# Proiect_TSC.net
KiCad netlist of a schematic drawn in EAGLE
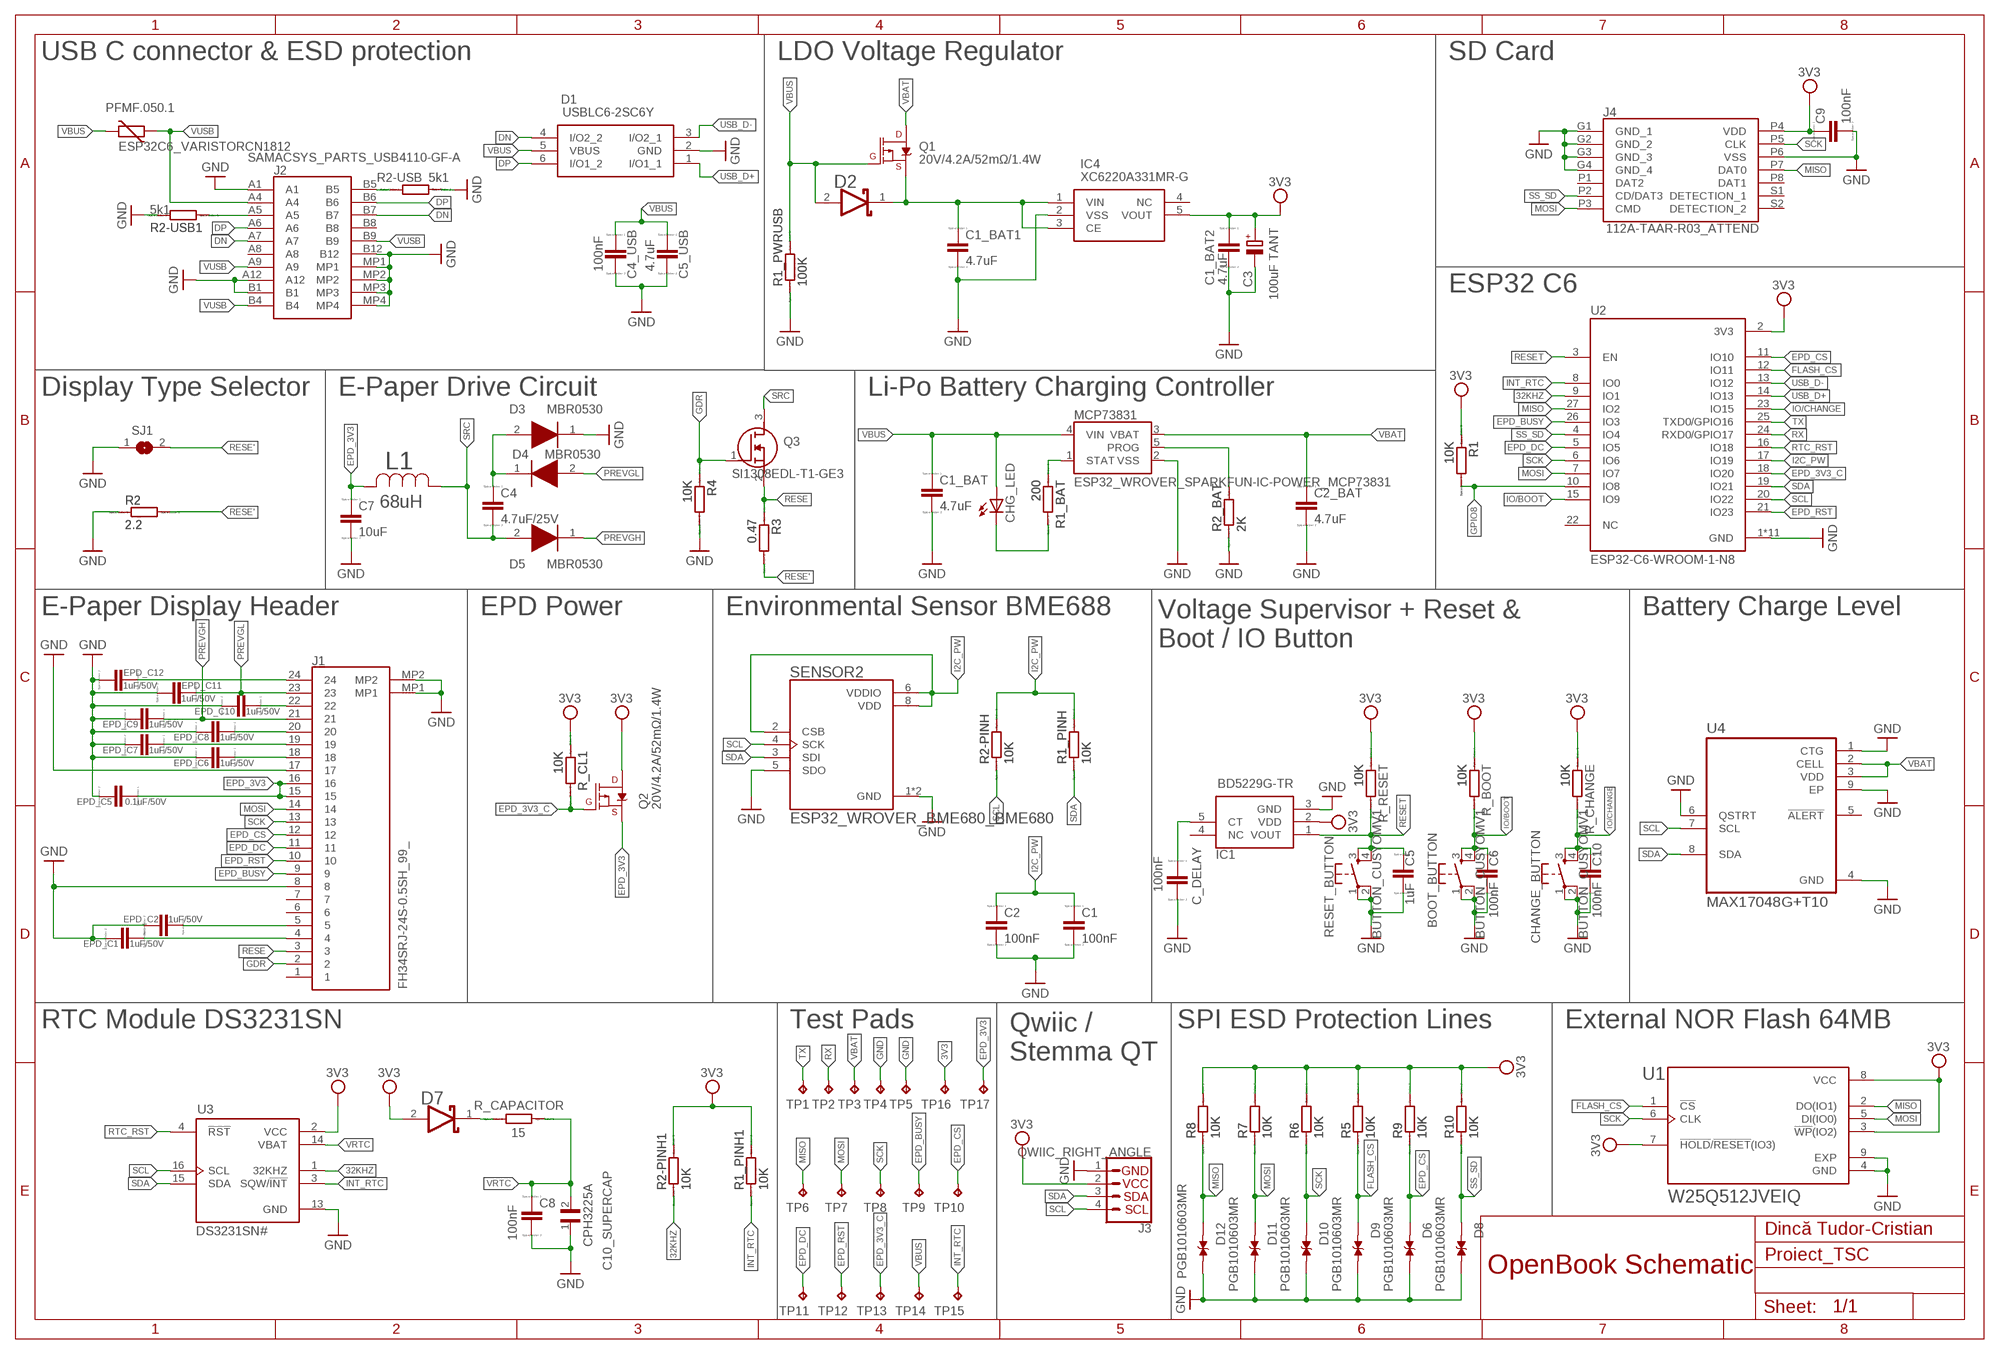
[diagram p0: schematic, sheet 1]

(export (version "E")
  (design (tool "Eeschema 10.0.6"))
  (components
    (comp (ref "BOOT_BUTTON")
      (value "BUTTON_CUSYOMV1")
      (footprint "eagle-import:MYBUTTON")
      (libsource (lib "eagle-import") (part "BUTTON_CUSYOMV1"))
    )
    (comp (ref "C1")
      (value "100nF")
      (footprint "eagle-import:EAGLE-LTSPICE_C0402")
      (libsource (lib "eagle-import") (part "EAGLE-LTSPICE_CC0402"))
    )
    (comp (ref "C1_BAT")
      (value "4.7uF")
      (footprint "eagle-import:EAGLE-LTSPICE_C0402")
      (libsource (lib "eagle-import") (part "EAGLE-LTSPICE_CC0402"))
    )
    (comp (ref "C1_BAT1")
      (value "4.7uF")
      (footprint "eagle-import:EAGLE-LTSPICE_C0402")
      (libsource (lib "eagle-import") (part "ESP32_WROVER_EAGLE-LTSPICE_CC0402"))
    )
    (comp (ref "C1_BAT2")
      (value "4.7uF")
      (footprint "eagle-import:EAGLE-LTSPICE_C0402")
      (libsource (lib "eagle-import") (part "ESP32_WROVER_EAGLE-LTSPICE_CC0402"))
    )
    (comp (ref "C2")
      (value "100nF")
      (footprint "eagle-import:EAGLE-LTSPICE_C0402")
      (libsource (lib "eagle-import") (part "EAGLE-LTSPICE_CC0402"))
    )
    (comp (ref "C2_BAT")
      (value "4.7uF")
      (footprint "eagle-import:EAGLE-LTSPICE_C0402")
      (libsource (lib "eagle-import") (part "EAGLE-LTSPICE_CC0402"))
    )
    (comp (ref "C3")
      (value "100uF TANT")
      (footprint "eagle-import:RCL_CT3528")
      (libsource (lib "eagle-import") (part "RCL_CPOL-EUCT3528"))
    )
    (comp (ref "C4")
      (value "4.7uF/25V")
      (footprint "eagle-import:EAGLE-LTSPICE_C0402")
      (libsource (lib "eagle-import") (part "EAGLE-LTSPICE_CC0402"))
    )
    (comp (ref "C4_USB")
      (value "100nF")
      (footprint "eagle-import:EAGLE-LTSPICE_C0402")
      (libsource (lib "eagle-import") (part "ESP32_WROVER_EAGLE-LTSPICE_CC0402"))
    )
    (comp (ref "C5")
      (value "1uF")
      (footprint "eagle-import:EAGLE-LTSPICE_C0402")
      (libsource (lib "eagle-import") (part "EAGLE-LTSPICE_CC0402"))
    )
    (comp (ref "C5_USB")
      (value "4.7uF")
      (footprint "eagle-import:EAGLE-LTSPICE_C0402")
      (libsource (lib "eagle-import") (part "ESP32_WROVER_EAGLE-LTSPICE_CC0402"))
    )
    (comp (ref "C6")
      (value "100nF")
      (footprint "eagle-import:EAGLE-LTSPICE_C0402")
      (libsource (lib "eagle-import") (part "EAGLE-LTSPICE_CC0402"))
    )
    (comp (ref "C7")
      (value "10uF")
      (footprint "eagle-import:EAGLE-LTSPICE_C0402")
      (libsource (lib "eagle-import") (part "EAGLE-LTSPICE_CC0402"))
    )
    (comp (ref "C8")
      (value "100nF")
      (footprint "eagle-import:EAGLE-LTSPICE_C0402")
      (libsource (lib "eagle-import") (part "EAGLE-LTSPICE_CC0402"))
    )
    (comp (ref "C9")
      (value "100nF")
      (footprint "eagle-import:EAGLE-LTSPICE_C0402")
      (libsource (lib "eagle-import") (part "ESP32_WROVER_EAGLE-LTSPICE_CC0402"))
    )
    (comp (ref "C10")
      (value "100nF")
      (footprint "eagle-import:EAGLE-LTSPICE_C0402")
      (libsource (lib "eagle-import") (part "EAGLE-LTSPICE_CC0402"))
    )
    (comp (ref "C10_SUPERCAP")
      (value "CPH3225A")
      (footprint "eagle-import:CAPCP3225X100N")
      (fields (field (name "MF") "Seiko Instruments"))
      (libsource (lib "eagle-import") (part "CPH3225A"))
    )
    (comp (ref "CHANGE_BUTTON")
      (value "BUTTON_CUSYOMV1")
      (footprint "eagle-import:MYBUTTON")
      (libsource (lib "eagle-import") (part "BUTTON_CUSYOMV1"))
    )
    (comp (ref "CHG_LED")
      (value "ADAFRUIT_LEDCHIP-LED0603")
      (footprint "eagle-import:ADAFRUIT_CHIP-LED0603")
      (libsource (lib "eagle-import") (part "ADAFRUIT_LEDCHIP-LED0603"))
    )
    (comp (ref "C_DELAY")
      (value "100nF")
      (footprint "eagle-import:EAGLE-LTSPICE_C0402")
      (libsource (lib "eagle-import") (part "EAGLE-LTSPICE_CC0402"))
    )
    (comp (ref "D1")
      (value "USBLC6-2SC6Y")
      (footprint "eagle-import:SOT95P280X145-6N")
      (fields (field (name "MF") "STMicroelectronics"))
      (libsource (lib "eagle-import") (part "USBLC6-2SC6Y"))
    )
    (comp (ref "D2")
      (value "ESP32_WROVER_AVX---SD0805S020S1R0_AVX_SD0805S020S1R0_0_0AVX_SD0805S020S1R0_0_0")
      (footprint "eagle-import:ESP32_WROVER_AVX---SD0805S020S1R0_AVX_SD0805S020S1R0_0")
      (fields
        (field (name "DIGIKEY_PART_NUMBER") "478-7800-1-ND")
        (field (name "MF") "AVX")
        (field (name "MOUSER_PART_NUMBER") "581-SD0805S020S1R0")
      )
      (libsource (lib "eagle-import") (part "ESP32_WROVER_AVX---SD0805S020S1R0_AVX_SD0805S020S1R0_0_0AVX_SD0805S020S1R0_0_0"))
    )
    (comp (ref "D3")
      (value "MBR0530")
      (footprint "eagle-import:SOD3716X135N")
      (fields (field (name "MF") "ON Semiconductor"))
      (libsource (lib "eagle-import") (part "MBR0530"))
    )
    (comp (ref "D4")
      (value "MBR0530")
      (footprint "eagle-import:SOD3716X135N")
      (fields (field (name "MF") "ON Semiconductor"))
      (libsource (lib "eagle-import") (part "MBR0530"))
    )
    (comp (ref "D5")
      (value "MBR0530")
      (footprint "eagle-import:SOD3716X135N")
      (fields (field (name "MF") "ON Semiconductor"))
      (libsource (lib "eagle-import") (part "MBR0530"))
    )
    (comp (ref "D6")
      (value "PGB1010603MR")
      (footprint "eagle-import:DIOC1608X36N")
      (fields (field (name "MF") "Littelfuse Inc."))
      (libsource (lib "eagle-import") (part "PGB1010603MR"))
    )
    (comp (ref "D7")
      (value "ESP32_WROVER_AVX---SD0805S020S1R0_AVX_SD0805S020S1R0_0_0AVX_SD0805S020S1R0_0_0")
      (footprint "eagle-import:ESP32_WROVER_AVX---SD0805S020S1R0_AVX_SD0805S020S1R0_0")
      (fields
        (field (name "DIGIKEY_PART_NUMBER") "478-7800-1-ND")
        (field (name "MF") "AVX")
        (field (name "MOUSER_PART_NUMBER") "581-SD0805S020S1R0")
      )
      (libsource (lib "eagle-import") (part "ESP32_WROVER_AVX---SD0805S020S1R0_AVX_SD0805S020S1R0_0_0AVX_SD0805S020S1R0_0_0"))
    )
    (comp (ref "D8")
      (value "PGB1010603MR")
      (footprint "eagle-import:DIOC1608X36N")
      (fields (field (name "MF") "Littelfuse Inc."))
      (libsource (lib "eagle-import") (part "PGB1010603MR"))
    )
    (comp (ref "D9")
      (value "PGB1010603MR")
      (footprint "eagle-import:DIOC1608X36N")
      (fields (field (name "MF") "Littelfuse Inc."))
      (libsource (lib "eagle-import") (part "PGB1010603MR"))
    )
    (comp (ref "D10")
      (value "PGB1010603MR")
      (footprint "eagle-import:DIOC1608X36N")
      (fields (field (name "MF") "Littelfuse Inc."))
      (libsource (lib "eagle-import") (part "PGB1010603MR"))
    )
    (comp (ref "D11")
      (value "PGB1010603MR")
      (footprint "eagle-import:DIOC1608X36N")
      (fields (field (name "MF") "Littelfuse Inc."))
      (libsource (lib "eagle-import") (part "PGB1010603MR"))
    )
    (comp (ref "D12")
      (value "PGB1010603MR")
      (footprint "eagle-import:DIOC1608X36N")
      (fields (field (name "MF") "Littelfuse Inc."))
      (libsource (lib "eagle-import") (part "PGB1010603MR"))
    )
    (comp (ref "EPD_C1")
      (value "1uF/50V")
      (footprint "eagle-import:EAGLE-LTSPICE_C0402")
      (libsource (lib "eagle-import") (part "EAGLE-LTSPICE_CC0402"))
    )
    (comp (ref "EPD_C2")
      (value "1uF/50V")
      (footprint "eagle-import:EAGLE-LTSPICE_C0402")
      (libsource (lib "eagle-import") (part "EAGLE-LTSPICE_CC0402"))
    )
    (comp (ref "EPD_C5")
      (value "0.1uF/50V")
      (footprint "eagle-import:EAGLE-LTSPICE_C0402")
      (libsource (lib "eagle-import") (part "EAGLE-LTSPICE_CC0402"))
    )
    (comp (ref "EPD_C6")
      (value "1uF/50V")
      (footprint "eagle-import:EAGLE-LTSPICE_C0402")
      (libsource (lib "eagle-import") (part "EAGLE-LTSPICE_CC0402"))
    )
    (comp (ref "EPD_C7")
      (value "1uF/50V")
      (footprint "eagle-import:EAGLE-LTSPICE_C0402")
      (libsource (lib "eagle-import") (part "EAGLE-LTSPICE_CC0402"))
    )
    (comp (ref "EPD_C8")
      (value "1uF/50V")
      (footprint "eagle-import:EAGLE-LTSPICE_C0402")
      (libsource (lib "eagle-import") (part "EAGLE-LTSPICE_CC0402"))
    )
    (comp (ref "EPD_C9")
      (value "1uF/50V")
      (footprint "eagle-import:EAGLE-LTSPICE_C0402")
      (libsource (lib "eagle-import") (part "EAGLE-LTSPICE_CC0402"))
    )
    (comp (ref "EPD_C10")
      (value "1uF/50V")
      (footprint "eagle-import:EAGLE-LTSPICE_C0402")
      (libsource (lib "eagle-import") (part "EAGLE-LTSPICE_CC0402"))
    )
    (comp (ref "EPD_C11")
      (value "1uF/50V")
      (footprint "eagle-import:EAGLE-LTSPICE_C0402")
      (libsource (lib "eagle-import") (part "EAGLE-LTSPICE_CC0402"))
    )
    (comp (ref "EPD_C12")
      (value "1uF/50V")
      (footprint "eagle-import:EAGLE-LTSPICE_C0402")
      (libsource (lib "eagle-import") (part "EAGLE-LTSPICE_CC0402"))
    )
    (comp (ref "IC1")
      (value "BD5229G-TR")
      (footprint "eagle-import:SOT95P280X125-5N")
      (fields (field (name "MOUSER_PART_NUMBER") "755-BD5229G-TR"))
      (libsource (lib "eagle-import") (part "BD5229G-TR"))
    )
    (comp (ref "IC4")
      (value "XC6220A331MR-G")
      (footprint "eagle-import:SOT95P280X120-5N")
      (fields (field (name "MOUSER_PART_NUMBER") "865-XC6220A331MR-G"))
      (libsource (lib "eagle-import") (part "XC6220A331MR-G"))
    )
    (comp (ref "J1")
      (value "FH34SRJ-24S-0.5SH_99_")
      (footprint "eagle-import:FH34SRJ24S05SH99")
      (fields
        (field (name "MANUFACTURER_PART_NUMBER") "FH34SRJ-24S-0.5SH(99)")
        (field (name "MOUSER_PART_NUMBER") "798-FH34SRJ24S05SH99")
      )
      (libsource (lib "eagle-import") (part "FH34SRJ-24S-0.5SH_99_"))
    )
    (comp (ref "J2")
      (value "SAMACSYS_PARTS_USB4110-GF-A")
      (footprint "eagle-import:SAMACSYS_PARTS_USB4110GFA")
      (fields
        (field (name "MANUFACTURER_PART_NUMBER") "USB4110-GF-A")
        (field (name "MOUSER_PART_NUMBER") "640-USB4110-GF-A")
      )
      (libsource (lib "eagle-import") (part "SAMACSYS_PARTS_USB4110-GF-A"))
    )
    (comp (ref "J3")
      (value "QWIIC_RIGHT_ANGLE")
      (footprint "eagle-import:JST04_1MM_RA")
      (libsource (lib "eagle-import") (part "QWIIC_CONNECTORJS-1MM"))
    )
    (comp (ref "J4")
      (value "112A-TAAR-R03_ATTEND")
      (footprint "eagle-import:112ATAARR03ATTEND")
      (fields (field (name "MANUFACTURER_PART_NUMBER") "112A-TAAR-R03 ATTEND"))
      (libsource (lib "eagle-import") (part "112A-TAAR-R03_ATTEND"))
    )
    (comp (ref "L1")
      (value "68uH")
      (footprint "eagle-import:IND_4828-WE-TPC_WRE")
      (fields
        (field (name "MANUFACTURER_PART_NUMBER") "744043680")
        (field (name "COPYRIGHT") "Copyright (C) 2024 Ultra Librarian. All rights reserved.")
      )
      (libsource (lib "eagle-import") (part "744043680IND_4828-WE-TPC_WRE"))
    )
    (comp (ref "MCP73831")
      (value "ESP32_WROVER_SPARKFUN-IC-POWER_MCP73831")
      (footprint "eagle-import:ESP32_WROVER_SPARKFUN-IC-POWER_SOT23-5")
      (libsource (lib "eagle-import") (part "ESP32_WROVER_SPARKFUN-IC-POWER_MCP73831"))
    )
    (comp (ref "PFMF.050.1")
      (value "ESP32C6_VARISTORCN1812")
      (footprint "eagle-import:ESP32C6_VARISTOR_CT_CN1812")
      (libsource (lib "eagle-import") (part "ESP32C6_VARISTORCN1812"))
    )
    (comp (ref "Q1")
      (value "20V/4.2A/52mΩ/1.4W")
      (footprint "eagle-import:ESP32_WROVER_SPARKFUN-DISCRETESEMI_SOT23-3")
      (libsource (lib "eagle-import") (part "ESP32_WROVER_SPARKFUN-DISCRETESEMI_MOSFET_PCH-DMG2305UX-7"))
    )
    (comp (ref "Q2")
      (value "20V/4.2A/52mΩ/1.4W")
      (footprint "eagle-import:ESP32_WROVER_SPARKFUN-DISCRETESEMI_SOT23-3")
      (libsource (lib "eagle-import") (part "ESP32_WROVER_SPARKFUN-DISCRETESEMI_MOSFET_PCH-DMG2305UX-7"))
    )
    (comp (ref "Q3")
      (value "SI1308EDL-T1-GE3")
      (footprint "eagle-import:SOT65P210X110-3N")
      (fields (field (name "MF") "Vishay Siliconix"))
      (libsource (lib "eagle-import") (part "SI1308EDL-T1-GE3"))
    )
    (comp (ref "R1")
      (value "10K")
      (footprint "eagle-import:ESP32_WROVER_EAGLE-LTSPICE_R0402")
      (libsource (lib "eagle-import") (part "ESP32_WROVER_EAGLE-LTSPICE_RR0402"))
    )
    (comp (ref "R1_BAT")
      (value "200")
      (footprint "eagle-import:ESP32_WROVER_EAGLE-LTSPICE_R0402")
      (libsource (lib "eagle-import") (part "ESP32_WROVER_EAGLE-LTSPICE_RR0402"))
    )
    (comp (ref "R1_PINH")
      (value "10K")
      (footprint "eagle-import:ESP32_WROVER_EAGLE-LTSPICE_R0402")
      (libsource (lib "eagle-import") (part "ESP32_WROVER_EAGLE-LTSPICE_RR0402"))
    )
    (comp (ref "R1_PINH1")
      (value "10K")
      (footprint "eagle-import:ESP32_WROVER_EAGLE-LTSPICE_R0402")
      (libsource (lib "eagle-import") (part "ESP32_WROVER_EAGLE-LTSPICE_RR0402"))
    )
    (comp (ref "R1_PWRUSB")
      (value "100K")
      (footprint "eagle-import:ESP32_WROVER_EAGLE-LTSPICE_R0402")
      (libsource (lib "eagle-import") (part "ESP32_WROVER_EAGLE-LTSPICE_RR0402"))
    )
    (comp (ref "R2")
      (value "2.2")
      (footprint "eagle-import:ESP32_WROVER_EAGLE-LTSPICE_R0402")
      (libsource (lib "eagle-import") (part "ESP32_WROVER_EAGLE-LTSPICE_RR0402"))
    )
    (comp (ref "R2-PINH")
      (value "10K")
      (footprint "eagle-import:ESP32_WROVER_EAGLE-LTSPICE_R0402")
      (libsource (lib "eagle-import") (part "ESP32_WROVER_EAGLE-LTSPICE_RR0402"))
    )
    (comp (ref "R2-PINH1")
      (value "10K")
      (footprint "eagle-import:ESP32_WROVER_EAGLE-LTSPICE_R0402")
      (libsource (lib "eagle-import") (part "ESP32_WROVER_EAGLE-LTSPICE_RR0402"))
    )
    (comp (ref "R2-USB")
      (value "5k1")
      (footprint "eagle-import:ESP32_WROVER_EAGLE-LTSPICE_R0402")
      (libsource (lib "eagle-import") (part "ESP32_WROVER_EAGLE-LTSPICE_RR0402"))
    )
    (comp (ref "R2-USB1")
      (value "5k1")
      (footprint "eagle-import:ESP32_WROVER_EAGLE-LTSPICE_R0402")
      (libsource (lib "eagle-import") (part "ESP32_WROVER_EAGLE-LTSPICE_RR0402"))
    )
    (comp (ref "R2_BAT")
      (value "2K")
      (footprint "eagle-import:ESP32_WROVER_EAGLE-LTSPICE_R0402")
      (libsource (lib "eagle-import") (part "ESP32_WROVER_EAGLE-LTSPICE_RR0402"))
    )
    (comp (ref "R3")
      (value "0.47")
      (footprint "eagle-import:ESP32_WROVER_EAGLE-LTSPICE_R0402")
      (libsource (lib "eagle-import") (part "ESP32_WROVER_EAGLE-LTSPICE_RR0402"))
    )
    (comp (ref "R4")
      (value "10K")
      (footprint "eagle-import:ESP32_WROVER_EAGLE-LTSPICE_R0402")
      (libsource (lib "eagle-import") (part "ESP32_WROVER_EAGLE-LTSPICE_RR0402"))
    )
    (comp (ref "R5")
      (value "10K")
      (footprint "eagle-import:ESP32_WROVER_EAGLE-LTSPICE_R0402")
      (libsource (lib "eagle-import") (part "ESP32_WROVER_EAGLE-LTSPICE_RR0402"))
    )
    (comp (ref "R6")
      (value "10K")
      (footprint "eagle-import:ESP32_WROVER_EAGLE-LTSPICE_R0402")
      (libsource (lib "eagle-import") (part "ESP32_WROVER_EAGLE-LTSPICE_RR0402"))
    )
    (comp (ref "R7")
      (value "10K")
      (footprint "eagle-import:ESP32_WROVER_EAGLE-LTSPICE_R0402")
      (libsource (lib "eagle-import") (part "ESP32_WROVER_EAGLE-LTSPICE_RR0402"))
    )
    (comp (ref "R8")
      (value "10K")
      (footprint "eagle-import:ESP32_WROVER_EAGLE-LTSPICE_R0402")
      (libsource (lib "eagle-import") (part "ESP32_WROVER_EAGLE-LTSPICE_RR0402"))
    )
    (comp (ref "R9")
      (value "10K")
      (footprint "eagle-import:ESP32_WROVER_EAGLE-LTSPICE_R0402")
      (libsource (lib "eagle-import") (part "ESP32_WROVER_EAGLE-LTSPICE_RR0402"))
    )
    (comp (ref "R10")
      (value "10K")
      (footprint "eagle-import:ESP32_WROVER_EAGLE-LTSPICE_R0402")
      (libsource (lib "eagle-import") (part "ESP32_WROVER_EAGLE-LTSPICE_RR0402"))
    )
    (comp (ref "RESET_BUTTON")
      (value "BUTTON_CUSYOMV1")
      (footprint "eagle-import:MYBUTTON")
      (libsource (lib "eagle-import") (part "BUTTON_CUSYOMV1"))
    )
    (comp (ref "R_BOOT")
      (value "10K")
      (footprint "eagle-import:ESP32_WROVER_EAGLE-LTSPICE_R0402")
      (libsource (lib "eagle-import") (part "ESP32_WROVER_EAGLE-LTSPICE_RR0402"))
    )
    (comp (ref "R_CAPACITOR")
      (value "15")
      (footprint "eagle-import:ESP32_WROVER_EAGLE-LTSPICE_R0402")
      (libsource (lib "eagle-import") (part "ESP32_WROVER_EAGLE-LTSPICE_RR0402"))
    )
    (comp (ref "R_CHANGE")
      (value "10K")
      (footprint "eagle-import:ESP32_WROVER_EAGLE-LTSPICE_R0402")
      (libsource (lib "eagle-import") (part "ESP32_WROVER_EAGLE-LTSPICE_RR0402"))
    )
    (comp (ref "R_CL1")
      (value "10K")
      (footprint "eagle-import:ESP32_WROVER_EAGLE-LTSPICE_R0402")
      (libsource (lib "eagle-import") (part "ESP32_WROVER_EAGLE-LTSPICE_RR0402"))
    )
    (comp (ref "R_RESET")
      (value "10K")
      (footprint "eagle-import:ESP32_WROVER_EAGLE-LTSPICE_R0402")
      (libsource (lib "eagle-import") (part "ESP32_WROVER_EAGLE-LTSPICE_RR0402"))
    )
    (comp (ref "SENSOR2")
      (value "ESP32_WROVER_BME680_BME680")
      (footprint "eagle-import:ESP32_WROVER_BME680_PSON80P300X300X100-8N")
      (fields (field (name "MF") "Bosch Sensortec") (field (name "MP") "BME680"))
      (libsource (lib "eagle-import") (part "ESP32_WROVER_BME680_BME680"))
    )
    (comp (ref "SJ1") (value "SJ") (footprint "eagle-import:SJ") (libsource (lib "eagle-import") (part "SJ")))
    (comp (ref "TP1")
      (value "TPTP20R")
      (footprint "eagle-import:TP20R")
      (libsource (lib "eagle-import") (part "TPTP20R"))
    )
    (comp (ref "TP2")
      (value "TPTP20R")
      (footprint "eagle-import:TP20R")
      (libsource (lib "eagle-import") (part "TPTP20R"))
    )
    (comp (ref "TP3")
      (value "TPTP20R")
      (footprint "eagle-import:TP20R")
      (libsource (lib "eagle-import") (part "TPTP20R"))
    )
    (comp (ref "TP4")
      (value "TPTP20R")
      (footprint "eagle-import:TP20R")
      (libsource (lib "eagle-import") (part "TPTP20R"))
    )
    (comp (ref "TP5")
      (value "TPTP20R")
      (footprint "eagle-import:TP20R")
      (libsource (lib "eagle-import") (part "TPTP20R"))
    )
    (comp (ref "TP6")
      (value "TPTP20R")
      (footprint "eagle-import:TP20R")
      (libsource (lib "eagle-import") (part "TPTP20R"))
    )
    (comp (ref "TP7")
      (value "TPTP20R")
      (footprint "eagle-import:TP20R")
      (libsource (lib "eagle-import") (part "TPTP20R"))
    )
    (comp (ref "TP8")
      (value "TPTP20R")
      (footprint "eagle-import:TP20R")
      (libsource (lib "eagle-import") (part "TPTP20R"))
    )
    (comp (ref "TP9")
      (value "TPTP20R")
      (footprint "eagle-import:TP20R")
      (libsource (lib "eagle-import") (part "TPTP20R"))
    )
    (comp (ref "TP10")
      (value "TPTP20R")
      (footprint "eagle-import:TP20R")
      (libsource (lib "eagle-import") (part "TPTP20R"))
    )
    (comp (ref "TP11")
      (value "TPTP20R")
      (footprint "eagle-import:TP20R")
      (libsource (lib "eagle-import") (part "TPTP20R"))
    )
    (comp (ref "TP12")
      (value "TPTP20R")
      (footprint "eagle-import:TP20R")
      (libsource (lib "eagle-import") (part "TPTP20R"))
    )
    (comp (ref "TP13")
      (value "TPTP20R")
      (footprint "eagle-import:TP20R")
      (libsource (lib "eagle-import") (part "TPTP20R"))
    )
    (comp (ref "TP14")
      (value "TPTP20R")
      (footprint "eagle-import:TP20R")
      (libsource (lib "eagle-import") (part "TPTP20R"))
    )
    (comp (ref "TP15")
      (value "TPTP20R")
      (footprint "eagle-import:TP20R")
      (libsource (lib "eagle-import") (part "TPTP20R"))
    )
    (comp (ref "TP16")
      (value "TPTP20R")
      (footprint "eagle-import:TP20R")
      (libsource (lib "eagle-import") (part "TPTP20R"))
    )
    (comp (ref "TP17")
      (value "TPTP20R")
      (footprint "eagle-import:TP20R")
      (libsource (lib "eagle-import") (part "TPTP20R"))
    )
    (comp (ref "U1")
      (value "W25Q512JVEIQ")
      (footprint "eagle-import:SON127P600X800X80-9N")
      (fields (field (name "MF") "Winbond Electronics"))
      (libsource (lib "eagle-import") (part "W25Q512JVEIQ"))
    )
    (comp (ref "U2")
      (value "ESP32-C6-WROOM-1-N8")
      (footprint "eagle-import:XCVR_ESP32-C6-WROOM-1-N8")
      (fields (field (name "MF") "Espressif Systems"))
      (libsource (lib "eagle-import") (part "ESP32-C6-WROOM-1-N8"))
    )
    (comp (ref "U3")
      (value "DS3231SN#")
      (footprint "eagle-import:SOIC127P1032X265-16N")
      (fields (field (name "MF") "Analog Devices"))
      (libsource (lib "eagle-import") (part "DS3231SN#"))
    )
    (comp (ref "U4")
      (value "MAX17048G+T10")
      (footprint "eagle-import:SON50P200X200X80-9N")
      (fields (field (name "MF") "Analog Devices"))
      (libsource (lib "eagle-import") (part "MAX17048G+T10"))
    )
  )
  (nets
    (net (code "1") (name "3V3") (class "Default")
      (node (ref "C1_BAT2") (pin "1") (pinfunction "1_1") (pintype "passive"))
      (node (ref "C3") (pin "+") (pinfunction "+_+") (pintype "passive"))
      (node (ref "C9") (pin "1") (pinfunction "1_1") (pintype "passive"))
      (node (ref "D7") (pin "2") (pinfunction "ANODE_2") (pintype "bidirectional"))
      (node (ref "IC1") (pin "2") (pinfunction "VDD_2") (pintype "bidirectional"))
      (node (ref "IC4") (pin "5") (pinfunction "VOUT_5") (pintype "bidirectional"))
      (node (ref "J3") (pin "2") (pinfunction "2_2") (pintype "power_in"))
      (node (ref "J4") (pin "P4") (pinfunction "VDD_P4") (pintype "bidirectional"))
      (node (ref "Q2") (pin "3") (pinfunction "D_3") (pintype "bidirectional"))
      (node (ref "R1") (pin "1") (pinfunction "1_1") (pintype "passive"))
      (node (ref "R10") (pin "2") (pinfunction "2_2") (pintype "passive"))
      (node (ref "R1_PINH1") (pin "2") (pinfunction "2_2") (pintype "passive"))
      (node (ref "R2-PINH1") (pin "2") (pinfunction "2_2") (pintype "passive"))
      (node (ref "R5") (pin "2") (pinfunction "2_2") (pintype "passive"))
      (node (ref "R6") (pin "2") (pinfunction "2_2") (pintype "passive"))
      (node (ref "R7") (pin "2") (pinfunction "2_2") (pintype "passive"))
      (node (ref "R8") (pin "2") (pinfunction "2_2") (pintype "passive"))
      (node (ref "R9") (pin "2") (pinfunction "2_2") (pintype "passive"))
      (node (ref "R_BOOT") (pin "1") (pinfunction "1_1") (pintype "passive"))
      (node (ref "R_CHANGE") (pin "1") (pinfunction "1_1") (pintype "passive"))
      (node (ref "R_CL1") (pin "1") (pinfunction "1_1") (pintype "passive"))
      (node (ref "R_RESET") (pin "1") (pinfunction "1_1") (pintype "passive"))
      (node (ref "TP16") (pin "TP") (pinfunction "TP_TP") (pintype "input"))
      (node (ref "U1") (pin "3") (pinfunction "~{WP}(IO2)_3") (pintype "bidirectional"))
      (node (ref "U1") (pin "7") (pinfunction "~{HOLD}/~{RESET}(IO3)_7") (pintype "bidirectional"))
      (node (ref "U1") (pin "8") (pinfunction "VCC_8") (pintype "power_in"))
      (node (ref "U2") (pin "2") (pinfunction "3V3_2") (pintype "power_in"))
      (node (ref "U3") (pin "2") (pinfunction "VCC_2") (pintype "power_in"))
    )
    (net (code "2") (name "32KHZ") (class "Default")
      (node (ref "R2-PINH1") (pin "1") (pinfunction "1_1") (pintype "passive"))
      (node (ref "U2") (pin "9") (pinfunction "IO1_9") (pintype "bidirectional"))
      (node (ref "U3") (pin "1") (pinfunction "32KHZ_1") (pintype "output"))
    )
    (net (code "3") (name "DN") (class "Default")
      (node (ref "D1") (pin "4") (pinfunction "I/O2_2_4") (pintype "bidirectional"))
      (node (ref "J2") (pin "A7") (pinfunction "A7_A7") (pintype "bidirectional"))
      (node (ref "J2") (pin "B7") (pinfunction "B7_B7") (pintype "bidirectional"))
    )
    (net (code "4") (name "DP") (class "Default")
      (node (ref "D1") (pin "6") (pinfunction "I/O1_2_6") (pintype "bidirectional"))
      (node (ref "J2") (pin "A6") (pinfunction "A6_A6") (pintype "bidirectional"))
      (node (ref "J2") (pin "B6") (pinfunction "B6_B6") (pintype "bidirectional"))
    )
    (net (code "5") (name "EPD_3V3") (class "Default")
      (node (ref "C7") (pin "1") (pinfunction "1_1") (pintype "passive"))
      (node (ref "EPD_C5") (pin "1") (pinfunction "1_1") (pintype "passive"))
      (node (ref "J1") (pin "15") (pinfunction "15_15") (pintype "bidirectional"))
      (node (ref "J1") (pin "16") (pinfunction "16_16") (pintype "bidirectional"))
      (node (ref "L1") (pin "2") (pinfunction "2_2") (pintype "passive"))
      (node (ref "Q2") (pin "2") (pinfunction "S_2") (pintype "bidirectional"))
      (node (ref "TP17") (pin "TP") (pinfunction "TP_TP") (pintype "input"))
    )
    (net (code "6") (name "EPD_3V3_C") (class "Default")
      (node (ref "Q2") (pin "1") (pinfunction "G_1") (pintype "bidirectional"))
      (node (ref "R_CL1") (pin "2") (pinfunction "2_2") (pintype "passive"))
      (node (ref "TP13") (pin "TP") (pinfunction "TP_TP") (pintype "input"))
      (node (ref "U2") (pin "18") (pinfunction "IO20_18") (pintype "bidirectional"))
    )
    (net (code "7") (name "EPD_BUSY") (class "Default")
      (node (ref "J1") (pin "9") (pinfunction "9_9") (pintype "bidirectional"))
      (node (ref "TP9") (pin "TP") (pinfunction "TP_TP") (pintype "input"))
      (node (ref "U2") (pin "26") (pinfunction "IO3_26") (pintype "bidirectional"))
    )
    (net (code "8") (name "EPD_CS") (class "Default")
      (node (ref "D6") (pin "1") (pinfunction "1_1") (pintype "passive"))
      (node (ref "J1") (pin "12") (pinfunction "12_12") (pintype "bidirectional"))
      (node (ref "R9") (pin "1") (pinfunction "1_1") (pintype "passive"))
      (node (ref "TP10") (pin "TP") (pinfunction "TP_TP") (pintype "input"))
      (node (ref "U2") (pin "11") (pinfunction "IO10_11") (pintype "bidirectional"))
    )
    (net (code "9") (name "EPD_DC") (class "Default")
      (node (ref "J1") (pin "11") (pinfunction "11_11") (pintype "bidirectional"))
      (node (ref "TP11") (pin "TP") (pinfunction "TP_TP") (pintype "input"))
      (node (ref "U2") (pin "5") (pinfunction "IO5_5") (pintype "bidirectional"))
    )
    (net (code "10") (name "EPD_RST") (class "Default")
      (node (ref "J1") (pin "10") (pinfunction "10_10") (pintype "bidirectional"))
      (node (ref "TP12") (pin "TP") (pinfunction "TP_TP") (pintype "input"))
      (node (ref "U2") (pin "21") (pinfunction "IO23_21") (pintype "bidirectional"))
    )
    (net (code "11") (name "FLASH_CS") (class "Default")
      (node (ref "D9") (pin "1") (pinfunction "1_1") (pintype "passive"))
      (node (ref "R5") (pin "1") (pinfunction "1_1") (pintype "passive"))
      (node (ref "U1") (pin "1") (pinfunction "~{CS}_1") (pintype "input"))
      (node (ref "U2") (pin "12") (pinfunction "IO11_12") (pintype "bidirectional"))
    )
    (net (code "12") (name "GDR") (class "Default")
      (node (ref "J1") (pin "2") (pinfunction "2_2") (pintype "bidirectional"))
      (node (ref "Q3") (pin "1") (pinfunction "G_1") (pintype "bidirectional"))
      (node (ref "R4") (pin "1") (pinfunction "1_1") (pintype "passive"))
    )
    (net (code "13") (name "GND") (class "Default")
      (node (ref "BOOT_BUTTON") (pin "1") (pinfunction "1_1") (pintype "passive"))
      (node (ref "BOOT_BUTTON") (pin "2") (pinfunction "2_2") (pintype "passive"))
      (node (ref "C1") (pin "2") (pinfunction "2_2") (pintype "passive"))
      (node (ref "C10") (pin "2") (pinfunction "2_2") (pintype "passive"))
      (node (ref "C10_SUPERCAP") (pin "1") (pinfunction "1_1") (pintype "passive"))
      (node (ref "C1_BAT") (pin "2") (pinfunction "2_2") (pintype "passive"))
      (node (ref "C1_BAT1") (pin "2") (pinfunction "2_2") (pintype "passive"))
      (node (ref "C1_BAT2") (pin "2") (pinfunction "2_2") (pintype "passive"))
      (node (ref "C2") (pin "2") (pinfunction "2_2") (pintype "passive"))
      (node (ref "C2_BAT") (pin "2") (pinfunction "2_2") (pintype "passive"))
      (node (ref "C3") (pin "-") (pinfunction "-_-") (pintype "passive"))
      (node (ref "C4_USB") (pin "2") (pinfunction "2_2") (pintype "passive"))
      (node (ref "C5") (pin "2") (pinfunction "2_2") (pintype "passive"))
      (node (ref "C5_USB") (pin "2") (pinfunction "2_2") (pintype "passive"))
      (node (ref "C6") (pin "2") (pinfunction "2_2") (pintype "passive"))
      (node (ref "C7") (pin "2") (pinfunction "2_2") (pintype "passive"))
      (node (ref "C8") (pin "2") (pinfunction "2_2") (pintype "passive"))
      (node (ref "C9") (pin "2") (pinfunction "2_2") (pintype "passive"))
      (node (ref "CHANGE_BUTTON") (pin "1") (pinfunction "1_1") (pintype "passive"))
      (node (ref "CHANGE_BUTTON") (pin "2") (pinfunction "2_2") (pintype "passive"))
      (node (ref "C_DELAY") (pin "2") (pinfunction "2_2") (pintype "passive"))
      (node (ref "D1") (pin "2") (pinfunction "GND_2") (pintype "bidirectional"))
      (node (ref "D10") (pin "2") (pinfunction "2_2") (pintype "passive"))
      (node (ref "D11") (pin "2") (pinfunction "2_2") (pintype "passive"))
      (node (ref "D12") (pin "2") (pinfunction "2_2") (pintype "passive"))
      (node (ref "D3") (pin "1") (pinfunction "K_1") (pintype "bidirectional"))
      (node (ref "D6") (pin "2") (pinfunction "2_2") (pintype "passive"))
      (node (ref "D8") (pin "2") (pinfunction "2_2") (pintype "passive"))
      (node (ref "D9") (pin "2") (pinfunction "2_2") (pintype "passive"))
      (node (ref "EPD_C1") (pin "2") (pinfunction "2_2") (pintype "passive"))
      (node (ref "EPD_C10") (pin "2") (pinfunction "2_2") (pintype "passive"))
      (node (ref "EPD_C11") (pin "2") (pinfunction "2_2") (pintype "passive"))
      (node (ref "EPD_C12") (pin "2") (pinfunction "2_2") (pintype "passive"))
      (node (ref "EPD_C2") (pin "2") (pinfunction "2_2") (pintype "passive"))
      (node (ref "EPD_C5") (pin "2") (pinfunction "2_2") (pintype "passive"))
      (node (ref "EPD_C6") (pin "2") (pinfunction "2_2") (pintype "passive"))
      (node (ref "EPD_C7") (pin "2") (pinfunction "2_2") (pintype "passive"))
      (node (ref "EPD_C8") (pin "2") (pinfunction "2_2") (pintype "passive"))
      (node (ref "EPD_C9") (pin "2") (pinfunction "2_2") (pintype "passive"))
      (node (ref "IC1") (pin "3") (pinfunction "GND_3") (pintype "bidirectional"))
      (node (ref "IC4") (pin "2") (pinfunction "VSS_2") (pintype "bidirectional"))
      (node (ref "J1") (pin "17") (pinfunction "17_17") (pintype "bidirectional"))
      (node (ref "J1") (pin "8") (pinfunction "8_8") (pintype "bidirectional"))
      (node (ref "J1") (pin "MP1") (pinfunction "MP1_MP1") (pintype "bidirectional"))
      (node (ref "J1") (pin "MP2") (pinfunction "MP2_MP2") (pintype "bidirectional"))
      (node (ref "J2") (pin "A1") (pinfunction "A1_A1") (pintype "bidirectional"))
      (node (ref "J2") (pin "A12") (pinfunction "A12_A12") (pintype "bidirectional"))
      (node (ref "J2") (pin "B1") (pinfunction "B1_B1") (pintype "bidirectional"))
      (node (ref "J2") (pin "B12") (pinfunction "B12_B12") (pintype "bidirectional"))
      (node (ref "J2") (pin "MP1") (pinfunction "MP1_MP1") (pintype "bidirectional"))
      (node (ref "J2") (pin "MP2") (pinfunction "MP2_MP2") (pintype "bidirectional"))
      (node (ref "J2") (pin "MP3") (pinfunction "MP3_MP3") (pintype "bidirectional"))
      (node (ref "J2") (pin "MP4") (pinfunction "MP4_MP4") (pintype "bidirectional"))
      (node (ref "J3") (pin "1") (pinfunction "1_1") (pintype "power_in"))
      (node (ref "J4") (pin "G1") (pinfunction "GND_1_G1") (pintype "bidirectional"))
      (node (ref "J4") (pin "G2") (pinfunction "GND_2_G2") (pintype "bidirectional"))
      (node (ref "J4") (pin "G3") (pinfunction "GND_3_G3") (pintype "bidirectional"))
      (node (ref "J4") (pin "G4") (pinfunction "GND_4_G4") (pintype "bidirectional"))
      (node (ref "J4") (pin "P6") (pinfunction "VSS_P6") (pintype "bidirectional"))
      (node (ref "MCP73831") (pin "2") (pinfunction "VSS_2") (pintype "power_in"))
      (node (ref "R1_PWRUSB") (pin "1") (pinfunction "1_1") (pintype "passive"))
      (node (ref "R2") (pin "1") (pinfunction "1_1") (pintype "passive"))
      (node (ref "R2-USB") (pin "2") (pinfunction "2_2") (pintype "passive"))
      (node (ref "R2-USB1") (pin "2") (pinfunction "2_2") (pintype "passive"))
      (node (ref "R2_BAT") (pin "1") (pinfunction "1_1") (pintype "passive"))
      (node (ref "R4") (pin "2") (pinfunction "2_2") (pintype "passive"))
      (node (ref "RESET_BUTTON") (pin "1") (pinfunction "1_1") (pintype "passive"))
      (node (ref "RESET_BUTTON") (pin "2") (pinfunction "2_2") (pintype "passive"))
      (node (ref "SENSOR2") (pin "1") (pinfunction "GND_1") (pintype "power_in"))
      (node (ref "SENSOR2") (pin "5") (pinfunction "SDO_5") (pintype "bidirectional"))
      (node (ref "SENSOR2") (pin "7") (pinfunction "GND_7") (pintype "power_in"))
      (node (ref "SJ1") (pin "1") (pinfunction "1_1") (pintype "passive"))
      (node (ref "TP4") (pin "TP") (pinfunction "TP_TP") (pintype "input"))
      (node (ref "TP5") (pin "TP") (pinfunction "TP_TP") (pintype "input"))
      (node (ref "U1") (pin "4") (pinfunction "GND_4") (pintype "power_in"))
      (node (ref "U1") (pin "9") (pinfunction "EXP_9") (pintype "passive"))
      (node (ref "U2") (pin "1") (pinfunction "GND_1") (pintype "power_in"))
      (node (ref "U2") (pin "28") (pinfunction "GND_28") (pintype "power_in"))
      (node (ref "U2") (pin "29_1") (pinfunction "GND_29_1") (pintype "power_in"))
      (node (ref "U2") (pin "29_2") (pinfunction "GND_29_2") (pintype "power_in"))
      (node (ref "U2") (pin "29_3") (pinfunction "GND_29_3") (pintype "power_in"))
      (node (ref "U2") (pin "29_4") (pinfunction "GND_29_4") (pintype "power_in"))
      (node (ref "U2") (pin "29_5") (pinfunction "GND_29_5") (pintype "power_in"))
      (node (ref "U2") (pin "29_6") (pinfunction "GND_29_6") (pintype "power_in"))
      (node (ref "U2") (pin "29_7") (pinfunction "GND_29_7") (pintype "power_in"))
      (node (ref "U2") (pin "29_8") (pinfunction "GND_29_8") (pintype "power_in"))
      (node (ref "U2") (pin "29_9") (pinfunction "GND_29_9") (pintype "power_in"))
      (node (ref "U3") (pin "13") (pinfunction "GND_13") (pintype "power_in"))
      (node (ref "U4") (pin "1") (pinfunction "CTG_1") (pintype "power_in"))
      (node (ref "U4") (pin "4") (pinfunction "GND_4") (pintype "power_in"))
      (node (ref "U4") (pin "6") (pinfunction "QSTRT_6") (pintype "input"))
      (node (ref "U4") (pin "9") (pinfunction "EP_9") (pintype "power_in"))
    )
    (net (code "14") (name "GPIO8") (class "Default")
      (node (ref "R1") (pin "2") (pinfunction "2_2") (pintype "passive"))
      (node (ref "U2") (pin "10") (pinfunction "IO8_10") (pintype "bidirectional"))
    )
    (net (code "15") (name "I2C_PW") (class "Default")
      (node (ref "C1") (pin "1") (pinfunction "1_1") (pintype "passive"))
      (node (ref "C2") (pin "1") (pinfunction "1_1") (pintype "passive"))
      (node (ref "R1_PINH") (pin "2") (pinfunction "2_2") (pintype "passive"))
      (node (ref "R2-PINH") (pin "2") (pinfunction "2_2") (pintype "passive"))
      (node (ref "SENSOR2") (pin "2") (pinfunction "CSB_2") (pintype "input"))
      (node (ref "SENSOR2") (pin "6") (pinfunction "VDDIO_6") (pintype "power_in"))
      (node (ref "SENSOR2") (pin "8") (pinfunction "VDD_8") (pintype "power_in"))
      (node (ref "U2") (pin "17") (pinfunction "IO19_17") (pintype "bidirectional"))
    )
    (net (code "16") (name "INT_RTC") (class "Default")
      (node (ref "R1_PINH1") (pin "1") (pinfunction "1_1") (pintype "passive"))
      (node (ref "TP15") (pin "TP") (pinfunction "TP_TP") (pintype "input"))
      (node (ref "U2") (pin "8") (pinfunction "IO0_8") (pintype "bidirectional"))
      (node (ref "U3") (pin "3") (pinfunction "SQW/~{INT}_3") (pintype "output"))
    )
    (net (code "17") (name "IO{slash}BOOT") (class "Default")
      (node (ref "BOOT_BUTTON") (pin "3") (pinfunction "3_3") (pintype "passive"))
      (node (ref "BOOT_BUTTON") (pin "4") (pinfunction "4_4") (pintype "passive"))
      (node (ref "C6") (pin "1") (pinfunction "1_1") (pintype "passive"))
      (node (ref "R_BOOT") (pin "2") (pinfunction "2_2") (pintype "passive"))
      (node (ref "U2") (pin "15") (pinfunction "IO9_15") (pintype "bidirectional"))
    )
    (net (code "18") (name "IO{slash}CHANGE") (class "Default")
      (node (ref "C10") (pin "1") (pinfunction "1_1") (pintype "passive"))
      (node (ref "CHANGE_BUTTON") (pin "3") (pinfunction "3_3") (pintype "passive"))
      (node (ref "CHANGE_BUTTON") (pin "4") (pinfunction "4_4") (pintype "passive"))
      (node (ref "R_CHANGE") (pin "2") (pinfunction "2_2") (pintype "passive"))
      (node (ref "U2") (pin "23") (pinfunction "IO15_23") (pintype "bidirectional"))
    )
    (net (code "19") (name "MISO") (class "Default")
      (node (ref "D12") (pin "1") (pinfunction "1_1") (pintype "passive"))
      (node (ref "J4") (pin "P7") (pinfunction "DAT0_P7") (pintype "bidirectional"))
      (node (ref "R8") (pin "1") (pinfunction "1_1") (pintype "passive"))
      (node (ref "TP6") (pin "TP") (pinfunction "TP_TP") (pintype "input"))
      (node (ref "U1") (pin "2") (pinfunction "DO(IO1)_2") (pintype "bidirectional"))
      (node (ref "U2") (pin "27") (pinfunction "IO2_27") (pintype "bidirectional"))
    )
    (net (code "20") (name "MOSI") (class "Default")
      (node (ref "D11") (pin "1") (pinfunction "1_1") (pintype "passive"))
      (node (ref "J1") (pin "14") (pinfunction "14_14") (pintype "bidirectional"))
      (node (ref "J4") (pin "P3") (pinfunction "CMD_P3") (pintype "bidirectional"))
      (node (ref "R7") (pin "1") (pinfunction "1_1") (pintype "passive"))
      (node (ref "TP7") (pin "TP") (pinfunction "TP_TP") (pintype "input"))
      (node (ref "U1") (pin "5") (pinfunction "DI(IO0)_5") (pintype "bidirectional"))
      (node (ref "U2") (pin "7") (pinfunction "IO7_7") (pintype "bidirectional"))
    )
    (net (code "21") (name "Net-(CHG_LED-PadC)") (class "Default")
      (node (ref "CHG_LED") (pin "C") (pinfunction "C_C") (pintype "passive"))
      (node (ref "R1_BAT") (pin "2") (pinfunction "2_2") (pintype "passive"))
    )
    (net (code "22") (name "Net-(D2-CATHODE)") (class "Default")
      (node (ref "C1_BAT1") (pin "1") (pinfunction "1_1") (pintype "passive"))
      (node (ref "D2") (pin "1") (pinfunction "CATHODE_1") (pintype "bidirectional"))
      (node (ref "IC4") (pin "1") (pinfunction "VIN_1") (pintype "bidirectional"))
      (node (ref "IC4") (pin "3") (pinfunction "CE_3") (pintype "bidirectional"))
      (node (ref "Q1") (pin "2") (pinfunction "S_2") (pintype "bidirectional"))
    )
    (net (code "23") (name "Net-(D3-A)") (class "Default")
      (node (ref "C4") (pin "1") (pinfunction "1_1") (pintype "passive"))
      (node (ref "D3") (pin "2") (pinfunction "A_2") (pintype "bidirectional"))
      (node (ref "D4") (pin "1") (pinfunction "K_1") (pintype "bidirectional"))
    )
    (net (code "24") (name "Net-(D7-CATHODE)") (class "Default")
      (node (ref "D7") (pin "1") (pinfunction "CATHODE_1") (pintype "bidirectional"))
      (node (ref "R_CAPACITOR") (pin "2") (pinfunction "2_2") (pintype "passive"))
    )
    (net (code "25") (name "Net-(EPD_C1-Pad1)") (class "Default")
      (node (ref "EPD_C1") (pin "1") (pinfunction "1_1") (pintype "passive"))
      (node (ref "J1") (pin "4") (pinfunction "4_4") (pintype "bidirectional"))
    )
    (net (code "26") (name "Net-(EPD_C2-Pad1)") (class "Default")
      (node (ref "EPD_C2") (pin "1") (pinfunction "1_1") (pintype "passive"))
      (node (ref "J1") (pin "5") (pinfunction "5_5") (pintype "bidirectional"))
    )
    (net (code "27") (name "Net-(EPD_C6-Pad1)") (class "Default")
      (node (ref "EPD_C6") (pin "1") (pinfunction "1_1") (pintype "passive"))
      (node (ref "J1") (pin "18") (pinfunction "18_18") (pintype "bidirectional"))
    )
    (net (code "28") (name "Net-(EPD_C7-Pad1)") (class "Default")
      (node (ref "EPD_C7") (pin "1") (pinfunction "1_1") (pintype "passive"))
      (node (ref "J1") (pin "19") (pinfunction "19_19") (pintype "bidirectional"))
    )
    (net (code "29") (name "Net-(EPD_C8-Pad1)") (class "Default")
      (node (ref "EPD_C8") (pin "1") (pinfunction "1_1") (pintype "passive"))
      (node (ref "J1") (pin "20") (pinfunction "20_20") (pintype "bidirectional"))
    )
    (net (code "30") (name "Net-(EPD_C10-Pad1)") (class "Default")
      (node (ref "EPD_C10") (pin "1") (pinfunction "1_1") (pintype "passive"))
      (node (ref "J1") (pin "22") (pinfunction "22_22") (pintype "bidirectional"))
    )
    (net (code "31") (name "Net-(EPD_C12-Pad1)") (class "Default")
      (node (ref "EPD_C12") (pin "1") (pinfunction "1_1") (pintype "passive"))
      (node (ref "J1") (pin "24") (pinfunction "24_24") (pintype "bidirectional"))
    )
    (net (code "32") (name "Net-(IC1-CT)") (class "Default")
      (node (ref "C_DELAY") (pin "1") (pinfunction "1_1") (pintype "passive"))
      (node (ref "IC1") (pin "5") (pinfunction "CT_5") (pintype "bidirectional"))
    )
    (net (code "33") (name "Net-(J2-PadA5)") (class "Default")
      (node (ref "J2") (pin "A5") (pinfunction "A5_A5") (pintype "bidirectional"))
      (node (ref "R2-USB1") (pin "1") (pinfunction "1_1") (pintype "passive"))
    )
    (net (code "34") (name "Net-(J2-PadB5)") (class "Default")
      (node (ref "J2") (pin "B5") (pinfunction "B5_B5") (pintype "bidirectional"))
      (node (ref "R2-USB") (pin "1") (pinfunction "1_1") (pintype "passive"))
    )
    (net (code "35") (name "Net-(MCP73831-PROG)") (class "Default")
      (node (ref "MCP73831") (pin "5") (pinfunction "PROG_5") (pintype "input"))
      (node (ref "R2_BAT") (pin "2") (pinfunction "2_2") (pintype "passive"))
    )
    (net (code "36") (name "Net-(MCP73831-STAT)") (class "Default")
      (node (ref "MCP73831") (pin "1") (pinfunction "STAT_1") (pintype "output"))
      (node (ref "R1_BAT") (pin "1") (pinfunction "1_1") (pintype "passive"))
    )
    (net (code "37") (name "PREVGH") (class "Default")
      (node (ref "D5") (pin "1") (pinfunction "K_1") (pintype "bidirectional"))
      (node (ref "EPD_C9") (pin "1") (pinfunction "1_1") (pintype "passive"))
      (node (ref "J1") (pin "21") (pinfunction "21_21") (pintype "bidirectional"))
    )
    (net (code "38") (name "PREVGL") (class "Default")
      (node (ref "D4") (pin "2") (pinfunction "A_2") (pintype "bidirectional"))
      (node (ref "EPD_C11") (pin "1") (pinfunction "1_1") (pintype "passive"))
      (node (ref "J1") (pin "23") (pinfunction "23_23") (pintype "bidirectional"))
    )
    (net (code "39") (name "RESE") (class "Default")
      (node (ref "J1") (pin "3") (pinfunction "3_3") (pintype "bidirectional"))
      (node (ref "Q3") (pin "2") (pinfunction "S_2") (pintype "bidirectional"))
      (node (ref "R3") (pin "1") (pinfunction "1_1") (pintype "passive"))
    )
    (net (code "40") (name "RESE'") (class "Default")
      (node (ref "R2") (pin "2") (pinfunction "2_2") (pintype "passive"))
      (node (ref "R3") (pin "2") (pinfunction "2_2") (pintype "passive"))
      (node (ref "SJ1") (pin "2") (pinfunction "2_2") (pintype "passive"))
    )
    (net (code "41") (name "RESET") (class "Default")
      (node (ref "C5") (pin "1") (pinfunction "1_1") (pintype "passive"))
      (node (ref "IC1") (pin "1") (pinfunction "VOUT_1") (pintype "bidirectional"))
      (node (ref "RESET_BUTTON") (pin "3") (pinfunction "3_3") (pintype "passive"))
      (node (ref "RESET_BUTTON") (pin "4") (pinfunction "4_4") (pintype "passive"))
      (node (ref "R_RESET") (pin "2") (pinfunction "2_2") (pintype "passive"))
      (node (ref "U2") (pin "3") (pinfunction "EN_3") (pintype "input"))
    )
    (net (code "42") (name "RTC_RST") (class "Default")
      (node (ref "U2") (pin "16") (pinfunction "IO18_16") (pintype "bidirectional"))
      (node (ref "U3") (pin "4") (pinfunction "~{RST}_4") (pintype "input"))
    )
    (net (code "43") (name "RX") (class "Default")
      (node (ref "TP2") (pin "TP") (pinfunction "TP_TP") (pintype "input"))
      (node (ref "U2") (pin "24") (pinfunction "RXD0/GPIO17_24") (pintype "bidirectional"))
    )
    (net (code "44") (name "SCK") (class "Default")
      (node (ref "D10") (pin "1") (pinfunction "1_1") (pintype "passive"))
      (node (ref "J1") (pin "13") (pinfunction "13_13") (pintype "bidirectional"))
      (node (ref "J4") (pin "P5") (pinfunction "CLK_P5") (pintype "bidirectional"))
      (node (ref "R6") (pin "1") (pinfunction "1_1") (pintype "passive"))
      (node (ref "TP8") (pin "TP") (pinfunction "TP_TP") (pintype "input"))
      (node (ref "U1") (pin "6") (pinfunction "CLK_6") (pintype "input"))
      (node (ref "U2") (pin "6") (pinfunction "IO6_6") (pintype "bidirectional"))
    )
    (net (code "45") (name "SCL") (class "Default")
      (node (ref "J3") (pin "4") (pinfunction "4_4") (pintype "passive"))
      (node (ref "R2-PINH") (pin "1") (pinfunction "1_1") (pintype "passive"))
      (node (ref "SENSOR2") (pin "4") (pinfunction "SCK_4") (pintype "input"))
      (node (ref "U2") (pin "20") (pinfunction "IO22_20") (pintype "bidirectional"))
      (node (ref "U3") (pin "16") (pinfunction "SCL_16") (pintype "input"))
      (node (ref "U4") (pin "7") (pinfunction "SCL_7") (pintype "input"))
    )
    (net (code "46") (name "SDA") (class "Default")
      (node (ref "J3") (pin "3") (pinfunction "3_3") (pintype "passive"))
      (node (ref "R1_PINH") (pin "1") (pinfunction "1_1") (pintype "passive"))
      (node (ref "SENSOR2") (pin "3") (pinfunction "SDI_3") (pintype "bidirectional"))
      (node (ref "U2") (pin "19") (pinfunction "IO21_19") (pintype "bidirectional"))
      (node (ref "U3") (pin "15") (pinfunction "SDA_15") (pintype "bidirectional"))
      (node (ref "U4") (pin "8") (pinfunction "SDA_8") (pintype "bidirectional"))
    )
    (net (code "47") (name "SRC") (class "Default")
      (node (ref "C4") (pin "2") (pinfunction "2_2") (pintype "passive"))
      (node (ref "D5") (pin "2") (pinfunction "A_2") (pintype "bidirectional"))
      (node (ref "L1") (pin "1") (pinfunction "1_1") (pintype "passive"))
      (node (ref "Q3") (pin "3") (pinfunction "D_3") (pintype "bidirectional"))
    )
    (net (code "48") (name "SS_SD") (class "Default")
      (node (ref "D8") (pin "1") (pinfunction "1_1") (pintype "passive"))
      (node (ref "J4") (pin "P2") (pinfunction "CD/DAT3_P2") (pintype "bidirectional"))
      (node (ref "R10") (pin "1") (pinfunction "1_1") (pintype "passive"))
      (node (ref "U2") (pin "4") (pinfunction "IO4_4") (pintype "bidirectional"))
    )
    (net (code "49") (name "TX") (class "Default")
      (node (ref "TP1") (pin "TP") (pinfunction "TP_TP") (pintype "input"))
      (node (ref "U2") (pin "25") (pinfunction "TXD0/GPIO16_25") (pintype "bidirectional"))
    )
    (net (code "50") (name "USB_D+") (class "Default")
      (node (ref "D1") (pin "1") (pinfunction "I/O1_1_1") (pintype "bidirectional"))
      (node (ref "U2") (pin "14") (pinfunction "IO13_14") (pintype "bidirectional"))
    )
    (net (code "51") (name "USB_D-") (class "Default")
      (node (ref "D1") (pin "3") (pinfunction "I/O2_1_3") (pintype "bidirectional"))
      (node (ref "U2") (pin "13") (pinfunction "IO12_13") (pintype "bidirectional"))
    )
    (net (code "52") (name "VBAT") (class "Default")
      (node (ref "C2_BAT") (pin "1") (pinfunction "1_1") (pintype "passive"))
      (node (ref "MCP73831") (pin "3") (pinfunction "VBAT_3") (pintype "power_in"))
      (node (ref "Q1") (pin "3") (pinfunction "D_3") (pintype "bidirectional"))
      (node (ref "TP3") (pin "TP") (pinfunction "TP_TP") (pintype "input"))
      (node (ref "U4") (pin "2") (pinfunction "CELL_2") (pintype "power_in"))
      (node (ref "U4") (pin "3") (pinfunction "VDD_3") (pintype "power_in"))
    )
    (net (code "53") (name "VBUS") (class "Default")
      (node (ref "C1_BAT") (pin "1") (pinfunction "1_1") (pintype "passive"))
      (node (ref "C4_USB") (pin "1") (pinfunction "1_1") (pintype "passive"))
      (node (ref "C5_USB") (pin "1") (pinfunction "1_1") (pintype "passive"))
      (node (ref "CHG_LED") (pin "A") (pinfunction "A_A") (pintype "passive"))
      (node (ref "D1") (pin "5") (pinfunction "VBUS_5") (pintype "bidirectional"))
      (node (ref "D2") (pin "2") (pinfunction "ANODE_2") (pintype "bidirectional"))
      (node (ref "MCP73831") (pin "4") (pinfunction "VIN_4") (pintype "power_in"))
      (node (ref "PFMF.050.1") (pin "2") (pinfunction "2_2") (pintype "passive"))
      (node (ref "Q1") (pin "1") (pinfunction "G_1") (pintype "bidirectional"))
      (node (ref "R1_PWRUSB") (pin "2") (pinfunction "2_2") (pintype "passive"))
      (node (ref "TP14") (pin "TP") (pinfunction "TP_TP") (pintype "input"))
    )
    (net (code "54") (name "VRTC") (class "Default")
      (node (ref "C10_SUPERCAP") (pin "2") (pinfunction "2_2") (pintype "passive"))
      (node (ref "C8") (pin "1") (pinfunction "1_1") (pintype "passive"))
      (node (ref "R_CAPACITOR") (pin "1") (pinfunction "1_1") (pintype "passive"))
      (node (ref "U3") (pin "14") (pinfunction "VBAT_14") (pintype "power_in"))
    )
    (net (code "55") (name "VUSB") (class "Default")
      (node (ref "J2") (pin "A4") (pinfunction "A4_A4") (pintype "bidirectional"))
      (node (ref "J2") (pin "A9") (pinfunction "A9_A9") (pintype "bidirectional"))
      (node (ref "J2") (pin "B4") (pinfunction "B4_B4") (pintype "bidirectional"))
      (node (ref "J2") (pin "B9") (pinfunction "B9_B9") (pintype "bidirectional"))
      (node (ref "PFMF.050.1") (pin "1") (pinfunction "1_1") (pintype "passive"))
    )
    (net (code "56") (name "unconnected-(IC1-NC-Pad4)") (class "Default")
      (node (ref "IC1") (pin "4") (pinfunction "NC_4") (pintype "no_connect"))
    )
    (net (code "57") (name "unconnected-(IC4-NC-Pad4)") (class "Default")
      (node (ref "IC4") (pin "4") (pinfunction "NC_4") (pintype "no_connect"))
    )
    (net (code "58") (name "unconnected-(J1-Pad1)") (class "Default")
      (node (ref "J1") (pin "1") (pinfunction "1_1") (pintype "bidirectional"))
    )
    (net (code "59") (name "unconnected-(J1-Pad6)") (class "Default")
      (node (ref "J1") (pin "6") (pinfunction "6_6") (pintype "bidirectional"))
    )
    (net (code "60") (name "unconnected-(J1-Pad7)") (class "Default")
      (node (ref "J1") (pin "7") (pinfunction "7_7") (pintype "bidirectional"))
    )
    (net (code "61") (name "unconnected-(J2-PadA8)") (class "Default")
      (node (ref "J2") (pin "A8") (pinfunction "A8_A8") (pintype "bidirectional"))
    )
    (net (code "62") (name "unconnected-(J2-PadB8)") (class "Default")
      (node (ref "J2") (pin "B8") (pinfunction "B8_B8") (pintype "bidirectional"))
    )
    (net (code "63") (name "unconnected-(J4-DAT1-PadP8)") (class "Default")
      (node (ref "J4") (pin "P8") (pinfunction "DAT1_P8") (pintype "bidirectional"))
    )
    (net (code "64") (name "unconnected-(J4-DAT2-PadP1)") (class "Default")
      (node (ref "J4") (pin "P1") (pinfunction "DAT2_P1") (pintype "bidirectional"))
    )
    (net (code "65") (name "unconnected-(J4-DETECTION_1-PadS1)") (class "Default")
      (node (ref "J4") (pin "S1") (pinfunction "DETECTION_1_S1") (pintype "bidirectional"))
    )
    (net (code "66") (name "unconnected-(J4-DETECTION_2-PadS2)") (class "Default")
      (node (ref "J4") (pin "S2") (pinfunction "DETECTION_2_S2") (pintype "bidirectional"))
    )
    (net (code "67") (name "unconnected-(U2-NC-Pad22)") (class "Default")
      (node (ref "U2") (pin "22") (pinfunction "NC_22") (pintype "no_connect"))
    )
    (net (code "68") (name "unconnected-(U4-~{ALERT}-Pad5)") (class "Default")
      (node (ref "U4") (pin "5") (pinfunction "~{ALERT}_5") (pintype "output"))
    )
  )
)
